# LED_board.net
KiCad netlist of a schematic drawn in Altium Designer
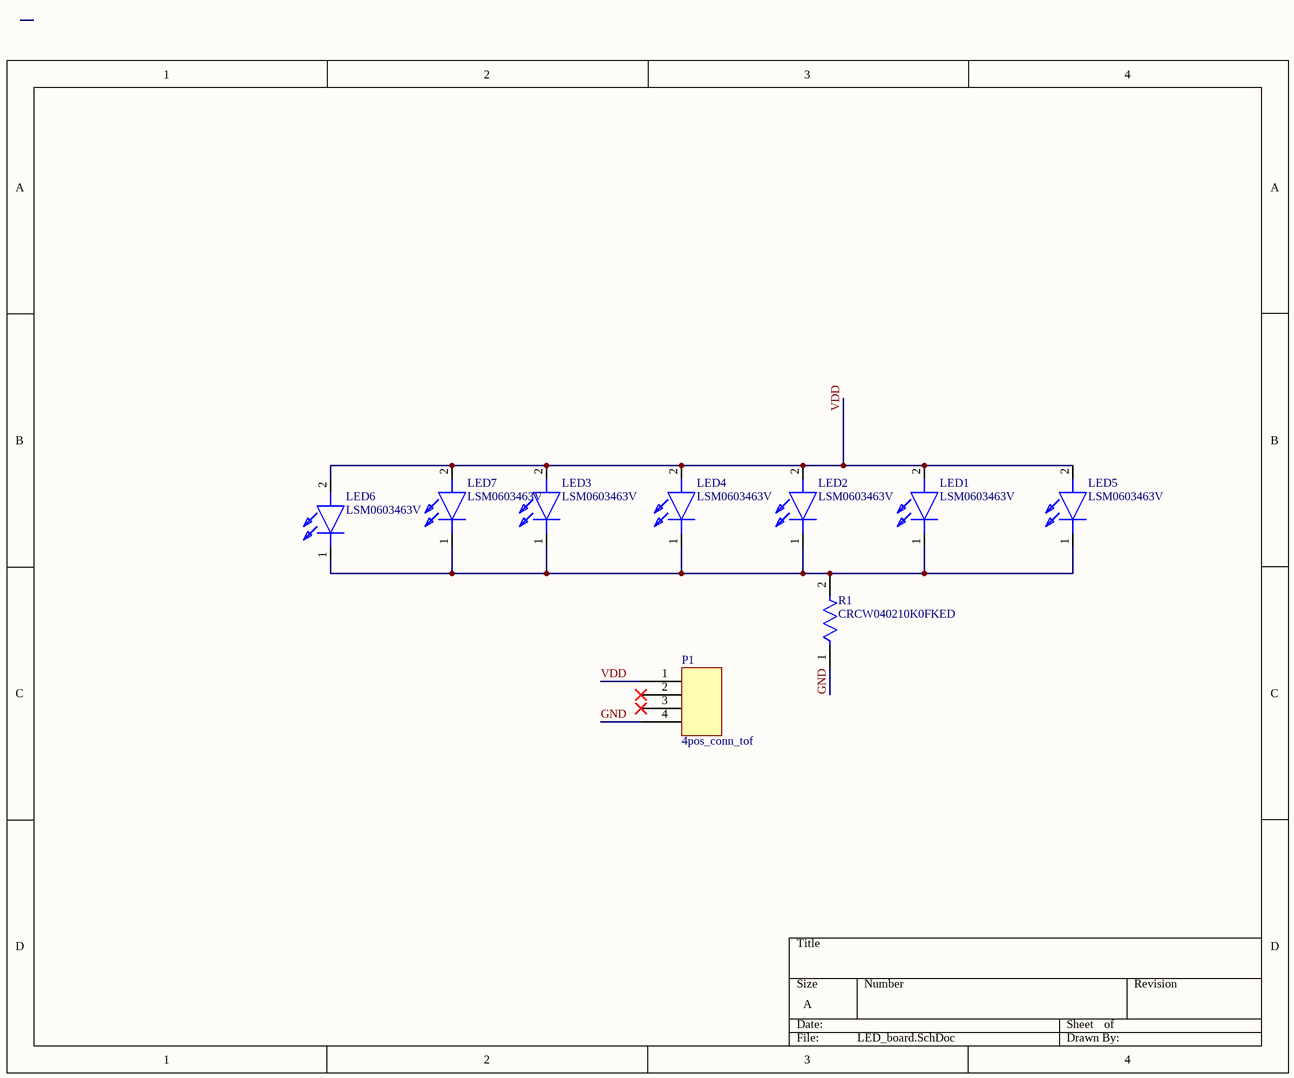
[diagram p0: LED_board.SchDoc]

(export (version "E")
  (design (tool "Eeschema 10.0.6"))
  (components
    (comp (ref "LED1")
      (value "LSM0603463V")
      (footprint "SamacSys:LSM0603463V")
      (description "LED")
      (fields (field (name "MOUSER PART NUMBER") "593-LSM0603463V"))
      (libsource (lib "*") (part "LSM0603463V"))
    )
    (comp (ref "LED2")
      (value "LSM0603463V")
      (footprint "SamacSys:LSM0603463V")
      (description "LED")
      (fields (field (name "MOUSER PART NUMBER") "593-LSM0603463V"))
      (libsource (lib "*") (part "LSM0603463V"))
    )
    (comp (ref "LED3")
      (value "LSM0603463V")
      (footprint "SamacSys:LSM0603463V")
      (description "LED")
      (fields (field (name "MOUSER PART NUMBER") "593-LSM0603463V"))
      (libsource (lib "*") (part "LSM0603463V"))
    )
    (comp (ref "LED4")
      (value "LSM0603463V")
      (footprint "SamacSys:LSM0603463V")
      (description "LED")
      (fields (field (name "MOUSER PART NUMBER") "593-LSM0603463V"))
      (libsource (lib "*") (part "LSM0603463V"))
    )
    (comp (ref "LED5")
      (value "LSM0603463V")
      (footprint "SamacSys:LSM0603463V")
      (description "LED")
      (fields (field (name "MOUSER PART NUMBER") "593-LSM0603463V"))
      (libsource (lib "*") (part "LSM0603463V"))
    )
    (comp (ref "LED6")
      (value "LSM0603463V")
      (footprint "SamacSys:LSM0603463V")
      (description "LED")
      (fields (field (name "MOUSER PART NUMBER") "593-LSM0603463V"))
      (libsource (lib "*") (part "LSM0603463V"))
    )
    (comp (ref "LED7")
      (value "LSM0603463V")
      (footprint "SamacSys:LSM0603463V")
      (description "LED")
      (fields (field (name "MOUSER PART NUMBER") "593-LSM0603463V"))
      (libsource (lib "*") (part "LSM0603463V"))
    )
    (comp (ref "P1")
      (value "4pos_conn_tof")
      (footprint "4pos_conn_tof")
      (libsource (lib "tof_board") (part "4pos_conn_tof"))
    )
    (comp (ref "R1")
      (value "CRCW040210K0FKED")
      (footprint "FP-CRCW0402-e3-IPC_B")
      (description "RES SMD 10K OHM 1% 1/16W 0402")
      (fields (field (name "TOLERANCE") "1%"))
      (libsource (lib "Altium Content Vault") (part "1029c3af85768c4190bb7ad29bc67b5"))
    )
  )
  (nets
    (net (code "1") (name "/GND") (class "Default")
      (node (ref "P1") (pin "4") (pinfunction "4_4") (pintype "passive"))
      (node (ref "R1") (pin "1") (pinfunction "1_1") (pintype "passive"))
    )
    (net (code "2") (name "/VDD") (class "Default")
      (node (ref "LED1") (pin "2") (pinfunction "A_2") (pintype "passive"))
      (node (ref "LED2") (pin "2") (pinfunction "A_2") (pintype "passive"))
      (node (ref "LED3") (pin "2") (pinfunction "A_2") (pintype "passive"))
      (node (ref "LED4") (pin "2") (pinfunction "A_2") (pintype "passive"))
      (node (ref "LED5") (pin "2") (pinfunction "A_2") (pintype "passive"))
      (node (ref "LED6") (pin "2") (pinfunction "A_2") (pintype "passive"))
      (node (ref "LED7") (pin "2") (pinfunction "A_2") (pintype "passive"))
      (node (ref "P1") (pin "1") (pinfunction "1_1") (pintype "passive"))
    )
    (net (code "3") (name "Net-(LED1-K)") (class "Default")
      (node (ref "LED1") (pin "1") (pinfunction "K_1") (pintype "passive"))
      (node (ref "LED2") (pin "1") (pinfunction "K_1") (pintype "passive"))
      (node (ref "LED3") (pin "1") (pinfunction "K_1") (pintype "passive"))
      (node (ref "LED4") (pin "1") (pinfunction "K_1") (pintype "passive"))
      (node (ref "LED5") (pin "1") (pinfunction "K_1") (pintype "passive"))
      (node (ref "LED6") (pin "1") (pinfunction "K_1") (pintype "passive"))
      (node (ref "LED7") (pin "1") (pinfunction "K_1") (pintype "passive"))
      (node (ref "R1") (pin "2") (pinfunction "2_2") (pintype "passive"))
    )
    (net (code "4") (name "unconnected-(P1-Pad2)") (class "Default")
      (node (ref "P1") (pin "2") (pinfunction "2_2") (pintype "passive+no_connect"))
    )
    (net (code "5") (name "unconnected-(P1-Pad3)") (class "Default")
      (node (ref "P1") (pin "3") (pinfunction "3_3") (pintype "passive+no_connect"))
    )
  )
)
